# OutputDigital.net
KiCad netlist of a schematic drawn in Altium Designer
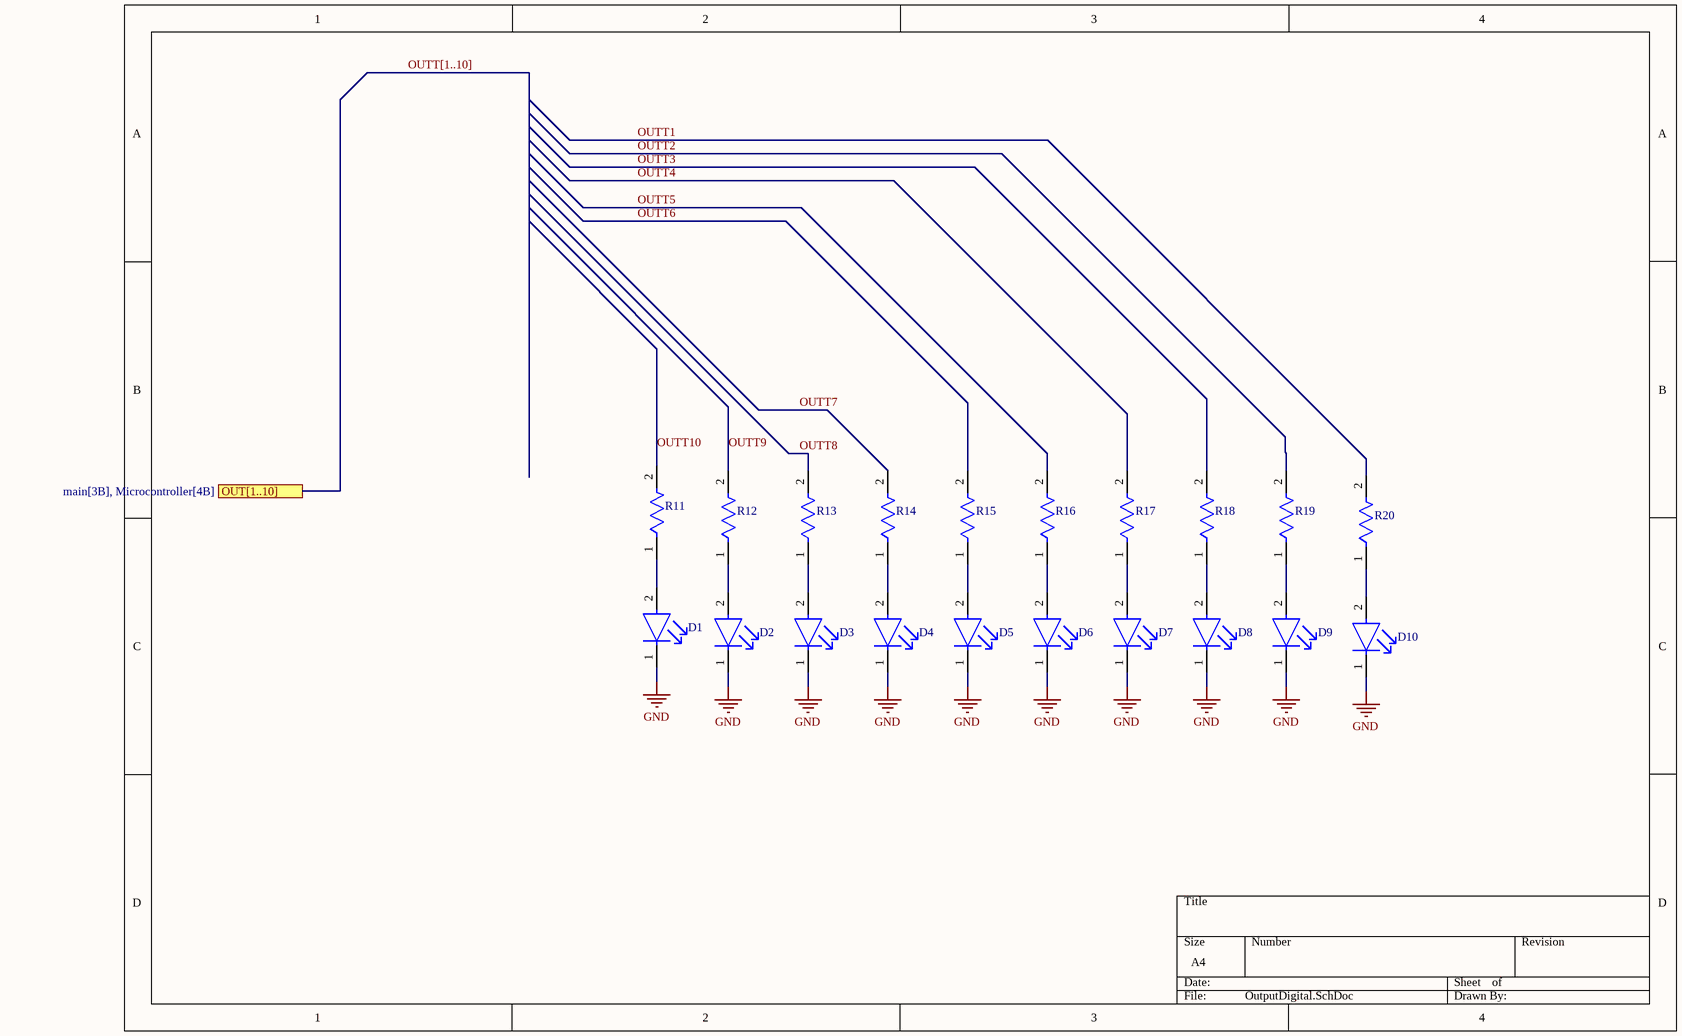
[diagram p0: OutputDigital.SchDoc]

(export (version "E")
  (design (tool "Eeschema 10.0.6"))
  (components
    (comp (ref "D1")
      (value "LTST-C230KRKT")
      (footprint "FP-LTST-C230KRKT-MFG")
      (description "LED RED CLEAR CHIP SMD")
      (libsource (lib "Ejemplo2") (part "CMP-22017-000041-1"))
    )
    (comp (ref "D2")
      (value "LTST-C230KRKT")
      (footprint "FP-LTST-C230KRKT-MFG")
      (description "LED RED CLEAR CHIP SMD")
      (libsource (lib "Ejemplo2") (part "CMP-22017-000041-1"))
    )
    (comp (ref "D3")
      (value "LTST-C230KRKT")
      (footprint "FP-LTST-C230KRKT-MFG")
      (description "LED RED CLEAR CHIP SMD")
      (libsource (lib "Ejemplo2") (part "CMP-22017-000041-1"))
    )
    (comp (ref "D4")
      (value "LTST-C230KRKT")
      (footprint "FP-LTST-C230KRKT-MFG")
      (description "LED RED CLEAR CHIP SMD")
      (libsource (lib "Ejemplo2") (part "CMP-22017-000041-1"))
    )
    (comp (ref "D5")
      (value "LTST-C230KRKT")
      (footprint "FP-LTST-C230KRKT-MFG")
      (description "LED RED CLEAR CHIP SMD")
      (libsource (lib "Ejemplo2") (part "CMP-22017-000041-1"))
    )
    (comp (ref "D6")
      (value "LTST-C230KRKT")
      (footprint "FP-LTST-C230KRKT-MFG")
      (description "LED RED CLEAR CHIP SMD")
      (libsource (lib "Ejemplo2") (part "CMP-22017-000041-1"))
    )
    (comp (ref "D7")
      (value "LTST-C230KRKT")
      (footprint "FP-LTST-C230KRKT-MFG")
      (description "LED RED CLEAR CHIP SMD")
      (libsource (lib "Ejemplo2") (part "CMP-22017-000041-1"))
    )
    (comp (ref "D8")
      (value "LTST-C230KRKT")
      (footprint "FP-LTST-C230KRKT-MFG")
      (description "LED RED CLEAR CHIP SMD")
      (libsource (lib "Ejemplo2") (part "CMP-22017-000041-1"))
    )
    (comp (ref "D9")
      (value "LTST-C230KRKT")
      (footprint "FP-LTST-C230KRKT-MFG")
      (description "LED RED CLEAR CHIP SMD")
      (libsource (lib "Ejemplo2") (part "CMP-22017-000041-1"))
    )
    (comp (ref "D10")
      (value "LTST-C230KRKT")
      (footprint "FP-LTST-C230KRKT-MFG")
      (description "LED RED CLEAR CHIP SMD")
      (libsource (lib "Ejemplo2") (part "CMP-22017-000041-1"))
    )
    (comp (ref "R11")
      (value "RT0805BRD07249RL")
      (footprint "FP-RT0805-MFG")
      (description "RES SMD 249 OHM 0.1% 1/8W 0805")
      (fields
        (field (name "OCTOPART") "https://octopart.com/rt0805brd07249rl-yageo-1410573")
        (field (name "MANUFACTURER") "Yageo")
      )
      (libsource (lib "Ejemplo2") (part "CMP-03412-035801-1"))
    )
    (comp (ref "R12")
      (value "RT0805BRD07249RL")
      (footprint "FP-RT0805-MFG")
      (description "RES SMD 249 OHM 0.1% 1/8W 0805")
      (fields
        (field (name "OCTOPART") "https://octopart.com/rt0805brd07249rl-yageo-1410573")
        (field (name "MANUFACTURER") "Yageo")
      )
      (libsource (lib "Ejemplo2") (part "CMP-03412-035801-1"))
    )
    (comp (ref "R13")
      (value "RT0805BRD07249RL")
      (footprint "FP-RT0805-MFG")
      (description "RES SMD 249 OHM 0.1% 1/8W 0805")
      (fields
        (field (name "OCTOPART") "https://octopart.com/rt0805brd07249rl-yageo-1410573")
        (field (name "MANUFACTURER") "Yageo")
      )
      (libsource (lib "Ejemplo2") (part "CMP-03412-035801-1"))
    )
    (comp (ref "R14")
      (value "RT0805BRD07249RL")
      (footprint "FP-RT0805-MFG")
      (description "RES SMD 249 OHM 0.1% 1/8W 0805")
      (fields
        (field (name "OCTOPART") "https://octopart.com/rt0805brd07249rl-yageo-1410573")
        (field (name "MANUFACTURER") "Yageo")
      )
      (libsource (lib "Ejemplo2") (part "CMP-03412-035801-1"))
    )
    (comp (ref "R15")
      (value "RT0805BRD07249RL")
      (footprint "FP-RT0805-MFG")
      (description "RES SMD 249 OHM 0.1% 1/8W 0805")
      (fields
        (field (name "OCTOPART") "https://octopart.com/rt0805brd07249rl-yageo-1410573")
        (field (name "MANUFACTURER") "Yageo")
      )
      (libsource (lib "Ejemplo2") (part "CMP-03412-035801-1"))
    )
    (comp (ref "R16")
      (value "RT0805BRD07249RL")
      (footprint "FP-RT0805-MFG")
      (description "RES SMD 249 OHM 0.1% 1/8W 0805")
      (fields
        (field (name "OCTOPART") "https://octopart.com/rt0805brd07249rl-yageo-1410573")
        (field (name "MANUFACTURER") "Yageo")
      )
      (libsource (lib "Ejemplo2") (part "CMP-03412-035801-1"))
    )
    (comp (ref "R17")
      (value "RT0805BRD07249RL")
      (footprint "FP-RT0805-MFG")
      (description "RES SMD 249 OHM 0.1% 1/8W 0805")
      (fields
        (field (name "OCTOPART") "https://octopart.com/rt0805brd07249rl-yageo-1410573")
        (field (name "MANUFACTURER") "Yageo")
      )
      (libsource (lib "Ejemplo2") (part "CMP-03412-035801-1"))
    )
    (comp (ref "R18")
      (value "RT0805BRD07249RL")
      (footprint "FP-RT0805-MFG")
      (description "RES SMD 249 OHM 0.1% 1/8W 0805")
      (fields
        (field (name "OCTOPART") "https://octopart.com/rt0805brd07249rl-yageo-1410573")
        (field (name "MANUFACTURER") "Yageo")
      )
      (libsource (lib "Ejemplo2") (part "CMP-03412-035801-1"))
    )
    (comp (ref "R19")
      (value "RT0805BRD07249RL")
      (footprint "FP-RT0805-MFG")
      (description "RES SMD 249 OHM 0.1% 1/8W 0805")
      (fields
        (field (name "OCTOPART") "https://octopart.com/rt0805brd07249rl-yageo-1410573")
        (field (name "MANUFACTURER") "Yageo")
      )
      (libsource (lib "Ejemplo2") (part "CMP-03412-035801-1"))
    )
    (comp (ref "R20")
      (value "RT0805BRD07249RL")
      (footprint "FP-RT0805-MFG")
      (description "RES SMD 249 OHM 0.1% 1/8W 0805")
      (fields
        (field (name "OCTOPART") "https://octopart.com/rt0805brd07249rl-yageo-1410573")
        (field (name "MANUFACTURER") "Yageo")
      )
      (libsource (lib "Ejemplo2") (part "CMP-03412-035801-1"))
    )
  )
  (nets
    (net (code "1") (name "/OUTT1") (class "Default")
      (node (ref "R20") (pin "2") (pinfunction "2_2") (pintype "passive"))
    )
    (net (code "2") (name "/OUTT2") (class "Default")
      (node (ref "R19") (pin "2") (pinfunction "2_2") (pintype "passive"))
    )
    (net (code "3") (name "/OUTT3") (class "Default")
      (node (ref "R18") (pin "2") (pinfunction "2_2") (pintype "passive"))
    )
    (net (code "4") (name "/OUTT4") (class "Default")
      (node (ref "R17") (pin "2") (pinfunction "2_2") (pintype "passive"))
    )
    (net (code "5") (name "/OUTT5") (class "Default")
      (node (ref "R16") (pin "2") (pinfunction "2_2") (pintype "passive"))
    )
    (net (code "6") (name "/OUTT6") (class "Default")
      (node (ref "R15") (pin "2") (pinfunction "2_2") (pintype "passive"))
    )
    (net (code "7") (name "/OUTT7") (class "Default")
      (node (ref "R14") (pin "2") (pinfunction "2_2") (pintype "passive"))
    )
    (net (code "8") (name "/OUTT8") (class "Default")
      (node (ref "R13") (pin "2") (pinfunction "2_2") (pintype "passive"))
    )
    (net (code "9") (name "/OUTT9") (class "Default")
      (node (ref "R12") (pin "2") (pinfunction "2_2") (pintype "passive"))
    )
    (net (code "10") (name "/OUTT10") (class "Default")
      (node (ref "R11") (pin "2") (pinfunction "2_2") (pintype "passive"))
    )
    (net (code "12") (name "GND") (class "Default")
      (node (ref "D1") (pin "1") (pinfunction "C_1") (pintype "passive"))
      (node (ref "D10") (pin "1") (pinfunction "C_1") (pintype "passive"))
      (node (ref "D2") (pin "1") (pinfunction "C_1") (pintype "passive"))
      (node (ref "D3") (pin "1") (pinfunction "C_1") (pintype "passive"))
      (node (ref "D4") (pin "1") (pinfunction "C_1") (pintype "passive"))
      (node (ref "D5") (pin "1") (pinfunction "C_1") (pintype "passive"))
      (node (ref "D6") (pin "1") (pinfunction "C_1") (pintype "passive"))
      (node (ref "D7") (pin "1") (pinfunction "C_1") (pintype "passive"))
      (node (ref "D8") (pin "1") (pinfunction "C_1") (pintype "passive"))
      (node (ref "D9") (pin "1") (pinfunction "C_1") (pintype "passive"))
    )
    (net (code "13") (name "Net-(D1-A)") (class "Default")
      (node (ref "D1") (pin "2") (pinfunction "A_2") (pintype "passive"))
      (node (ref "R11") (pin "1") (pinfunction "1_1") (pintype "passive"))
    )
    (net (code "14") (name "Net-(D2-A)") (class "Default")
      (node (ref "D2") (pin "2") (pinfunction "A_2") (pintype "passive"))
      (node (ref "R12") (pin "1") (pinfunction "1_1") (pintype "passive"))
    )
    (net (code "15") (name "Net-(D3-A)") (class "Default")
      (node (ref "D3") (pin "2") (pinfunction "A_2") (pintype "passive"))
      (node (ref "R13") (pin "1") (pinfunction "1_1") (pintype "passive"))
    )
    (net (code "16") (name "Net-(D4-A)") (class "Default")
      (node (ref "D4") (pin "2") (pinfunction "A_2") (pintype "passive"))
      (node (ref "R14") (pin "1") (pinfunction "1_1") (pintype "passive"))
    )
    (net (code "17") (name "Net-(D5-A)") (class "Default")
      (node (ref "D5") (pin "2") (pinfunction "A_2") (pintype "passive"))
      (node (ref "R15") (pin "1") (pinfunction "1_1") (pintype "passive"))
    )
    (net (code "18") (name "Net-(D6-A)") (class "Default")
      (node (ref "D6") (pin "2") (pinfunction "A_2") (pintype "passive"))
      (node (ref "R16") (pin "1") (pinfunction "1_1") (pintype "passive"))
    )
    (net (code "19") (name "Net-(D7-A)") (class "Default")
      (node (ref "D7") (pin "2") (pinfunction "A_2") (pintype "passive"))
      (node (ref "R17") (pin "1") (pinfunction "1_1") (pintype "passive"))
    )
    (net (code "20") (name "Net-(D8-A)") (class "Default")
      (node (ref "D8") (pin "2") (pinfunction "A_2") (pintype "passive"))
      (node (ref "R18") (pin "1") (pinfunction "1_1") (pintype "passive"))
    )
    (net (code "21") (name "Net-(D9-A)") (class "Default")
      (node (ref "D9") (pin "2") (pinfunction "A_2") (pintype "passive"))
      (node (ref "R19") (pin "1") (pinfunction "1_1") (pintype "passive"))
    )
    (net (code "22") (name "Net-(D10-A)") (class "Default")
      (node (ref "D10") (pin "2") (pinfunction "A_2") (pintype "passive"))
      (node (ref "R20") (pin "1") (pinfunction "1_1") (pintype "passive"))
    )
  )
)
